# vco__amp_twg.net
KiCad netlist of a schematic drawn in EAGLE
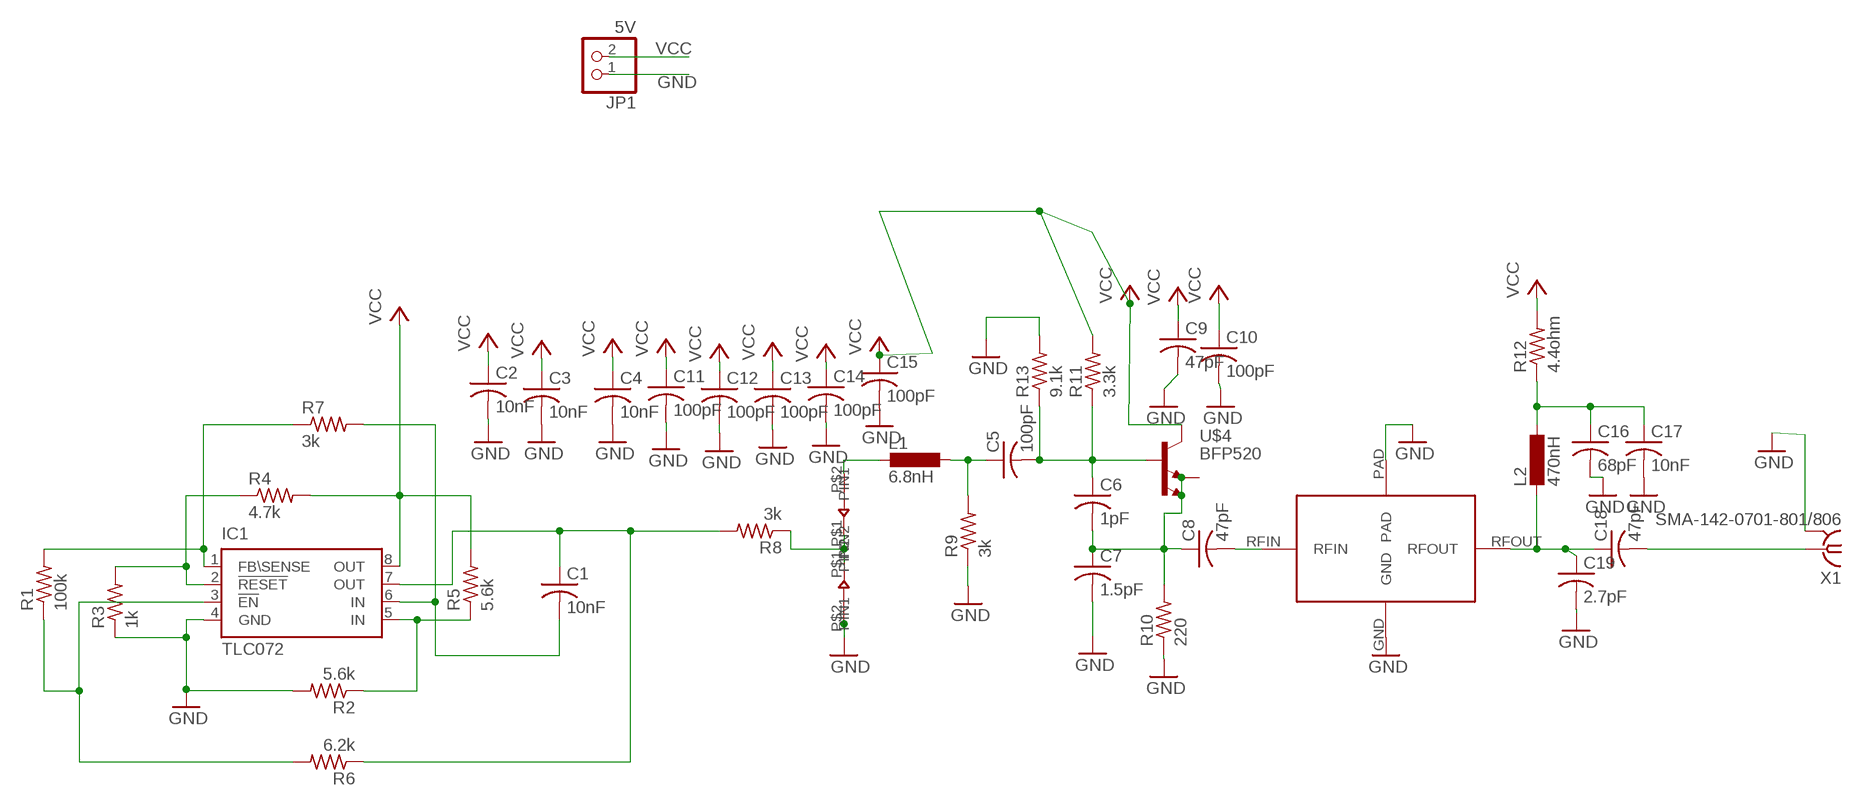
[diagram p0: schematic, sheet 1]

(export (version "E")
  (design (tool "Eeschema 10.0.6"))
  (components
    (comp (ref "C1")
      (value "10nF")
      (footprint "eagle-import:C0603")
      (libsource (lib "eagle-import") (part "resistor_C-USC0603"))
    )
    (comp (ref "C2")
      (value "10nF")
      (footprint "eagle-import:C0603")
      (libsource (lib "eagle-import") (part "resistor_C-USC0603"))
    )
    (comp (ref "C3")
      (value "10nF")
      (footprint "eagle-import:C0603")
      (libsource (lib "eagle-import") (part "resistor_C-USC0603"))
    )
    (comp (ref "C4")
      (value "10nF")
      (footprint "eagle-import:C0603")
      (libsource (lib "eagle-import") (part "resistor_C-USC0603"))
    )
    (comp (ref "C5")
      (value "100pF")
      (footprint "eagle-import:C0603")
      (libsource (lib "eagle-import") (part "resistor_C-USC0603"))
    )
    (comp (ref "C6")
      (value "1pF")
      (footprint "eagle-import:C0603")
      (libsource (lib "eagle-import") (part "resistor_C-USC0603"))
    )
    (comp (ref "C7")
      (value "1.5pF")
      (footprint "eagle-import:C0603")
      (libsource (lib "eagle-import") (part "resistor_C-USC0603"))
    )
    (comp (ref "C8")
      (value "47pF")
      (footprint "eagle-import:C0603")
      (libsource (lib "eagle-import") (part "resistor_C-USC0603"))
    )
    (comp (ref "C9")
      (value "47pF")
      (footprint "eagle-import:C0603")
      (libsource (lib "eagle-import") (part "resistor_C-USC0603"))
    )
    (comp (ref "C10")
      (value "100pF")
      (footprint "eagle-import:C0603")
      (libsource (lib "eagle-import") (part "resistor_C-USC0603"))
    )
    (comp (ref "C11")
      (value "100pF")
      (footprint "eagle-import:C0603")
      (libsource (lib "eagle-import") (part "resistor_C-USC0603"))
    )
    (comp (ref "C12")
      (value "100pF")
      (footprint "eagle-import:C0603")
      (libsource (lib "eagle-import") (part "resistor_C-USC0603"))
    )
    (comp (ref "C13")
      (value "100pF")
      (footprint "eagle-import:C0603")
      (libsource (lib "eagle-import") (part "resistor_C-USC0603"))
    )
    (comp (ref "C14")
      (value "100pF")
      (footprint "eagle-import:C0603")
      (libsource (lib "eagle-import") (part "resistor_C-USC0603"))
    )
    (comp (ref "C15")
      (value "100pF")
      (footprint "eagle-import:C0603")
      (libsource (lib "eagle-import") (part "resistor_C-USC0603"))
    )
    (comp (ref "C16")
      (value "68pF")
      (footprint "eagle-import:C0603")
      (libsource (lib "eagle-import") (part "resistor_C-USC0603"))
    )
    (comp (ref "C17")
      (value "10nF")
      (footprint "eagle-import:C0603")
      (libsource (lib "eagle-import") (part "resistor_C-USC0603"))
    )
    (comp (ref "C18")
      (value "47pF")
      (footprint "eagle-import:C0603")
      (libsource (lib "eagle-import") (part "resistor_C-USC0603"))
    )
    (comp (ref "C19")
      (value "2.7pF")
      (footprint "eagle-import:C0603")
      (libsource (lib "eagle-import") (part "C-USC0603"))
    )
    (comp (ref "IC1")
      (value "TLC072")
      (footprint "eagle-import:SOP-08")
      (fields (field (name "MF") "TEXAS INSTRUMENT CONNECTORS") (field (name "MPN") "TPS77301DGK"))
      (libsource (lib "eagle-import") (part "TPS77301"))
    )
    (comp (ref "JP1")
      (value "5V")
      (footprint "eagle-import:1X02")
      (libsource (lib "eagle-import") (part "PINHD-1X2"))
    )
    (comp (ref "L1")
      (value "6.8nH")
      (footprint "eagle-import:L0603")
      (libsource (lib "eagle-import") (part "L-EUL0603"))
    )
    (comp (ref "L2")
      (value "470nH")
      (footprint "eagle-import:L0603")
      (libsource (lib "eagle-import") (part "L-EUL0603"))
    )
    (comp (ref "R1")
      (value "100k")
      (footprint "eagle-import:R0603")
      (libsource (lib "eagle-import") (part "R-US_R0603"))
    )
    (comp (ref "R2")
      (value "5.6k")
      (footprint "eagle-import:R0603")
      (libsource (lib "eagle-import") (part "R-US_R0603"))
    )
    (comp (ref "R3")
      (value "1k")
      (footprint "eagle-import:R0603")
      (libsource (lib "eagle-import") (part "R-US_R0603"))
    )
    (comp (ref "R4")
      (value "4.7k")
      (footprint "eagle-import:R0603")
      (libsource (lib "eagle-import") (part "R-US_R0603"))
    )
    (comp (ref "R5")
      (value "5.6k")
      (footprint "eagle-import:R0603")
      (libsource (lib "eagle-import") (part "R-US_R0603"))
    )
    (comp (ref "R6")
      (value "6.2k")
      (footprint "eagle-import:R0603")
      (libsource (lib "eagle-import") (part "R-US_R0603"))
    )
    (comp (ref "R7")
      (value "3k")
      (footprint "eagle-import:R0603")
      (libsource (lib "eagle-import") (part "R-US_R0603"))
    )
    (comp (ref "R8")
      (value "3k")
      (footprint "eagle-import:R0603")
      (libsource (lib "eagle-import") (part "R-US_R0603"))
    )
    (comp (ref "R9")
      (value "3k")
      (footprint "eagle-import:R0603")
      (libsource (lib "eagle-import") (part "R-US_R0603"))
    )
    (comp (ref "R10")
      (value "220")
      (footprint "eagle-import:R0603")
      (libsource (lib "eagle-import") (part "R-US_R0603"))
    )
    (comp (ref "R11")
      (value "3.3k")
      (footprint "eagle-import:R0603")
      (libsource (lib "eagle-import") (part "R-US_R0603"))
    )
    (comp (ref "R12")
      (value "4.4ohm")
      (footprint "eagle-import:R0603")
      (libsource (lib "eagle-import") (part "R-US_R0603"))
    )
    (comp (ref "R13")
      (value "9.1k")
      (footprint "eagle-import:R0603")
      (libsource (lib "eagle-import") (part "R-US_R0603"))
    )
    (comp (ref "U$1")
      (value "BBY5702")
      (footprint "eagle-import:BBY5702")
      (libsource (lib "eagle-import") (part "BBY5702"))
    )
    (comp (ref "U$2")
      (value "MMG3001")
      (footprint "eagle-import:SOT-89")
      (libsource (lib "eagle-import") (part "MMG3001"))
    )
    (comp (ref "U$4")
      (value "BFP520")
      (footprint "eagle-import:SOT343")
      (libsource (lib "eagle-import") (part "BFP520"))
    )
    (comp (ref "U$5")
      (value "BBY5702")
      (footprint "eagle-import:BBY5702")
      (libsource (lib "eagle-import") (part "BBY5702"))
    )
    (comp (ref "X1")
      (value "SMA-142-0701-801/806")
      (footprint "eagle-import:J502-ND-142-0701-801_806")
      (fields (field (name "MF") "JOHNSON COMPONENTS") (field (name "MPN") "142-0701-801"))
      (libsource (lib "eagle-import") (part "SMA-142-0701-801/806"))
    )
  )
  (nets
    (net (code "1") (name "GND") (class "Default")
      (node (ref "C10") (pin "2") (pinfunction "2_2") (pintype "passive"))
      (node (ref "C11") (pin "2") (pinfunction "2_2") (pintype "passive"))
      (node (ref "C12") (pin "2") (pinfunction "2_2") (pintype "passive"))
      (node (ref "C13") (pin "2") (pinfunction "2_2") (pintype "passive"))
      (node (ref "C14") (pin "2") (pinfunction "2_2") (pintype "passive"))
      (node (ref "C15") (pin "2") (pinfunction "2_2") (pintype "passive"))
      (node (ref "C16") (pin "2") (pinfunction "2_2") (pintype "passive"))
      (node (ref "C17") (pin "2") (pinfunction "2_2") (pintype "passive"))
      (node (ref "C19") (pin "2") (pinfunction "2_2") (pintype "passive"))
      (node (ref "C2") (pin "2") (pinfunction "2_2") (pintype "passive"))
      (node (ref "C3") (pin "2") (pinfunction "2_2") (pintype "passive"))
      (node (ref "C4") (pin "2") (pinfunction "2_2") (pintype "passive"))
      (node (ref "C7") (pin "2") (pinfunction "2_2") (pintype "passive"))
      (node (ref "C9") (pin "2") (pinfunction "2_2") (pintype "passive"))
      (node (ref "IC1") (pin "4") (pinfunction "GND_4") (pintype "power_in"))
      (node (ref "JP1") (pin "1") (pinfunction "1_1") (pintype "passive"))
      (node (ref "R10") (pin "1") (pinfunction "1_1") (pintype "passive"))
      (node (ref "R13") (pin "2") (pinfunction "2_2") (pintype "passive"))
      (node (ref "R2") (pin "2") (pinfunction "2_2") (pintype "passive"))
      (node (ref "R3") (pin "1") (pinfunction "1_1") (pintype "passive"))
      (node (ref "R9") (pin "1") (pinfunction "1_1") (pintype "passive"))
      (node (ref "U$2") (pin "GND") (pinfunction "GND_GND") (pintype "bidirectional"))
      (node (ref "U$2") (pin "PAD") (pinfunction "PAD_PAD") (pintype "bidirectional"))
      (node (ref "U$5") (pin "P$2") (pinfunction "PIN2_P$2") (pintype "bidirectional"))
      (node (ref "X1") (pin "G@1") (pinfunction "2_G@1") (pintype "passive"))
      (node (ref "X1") (pin "G@2") (pinfunction "2_G@2") (pintype "passive"))
      (node (ref "X1") (pin "G@3") (pinfunction "2_G@3") (pintype "passive"))
      (node (ref "X1") (pin "G@4") (pinfunction "2_G@4") (pintype "passive"))
    )
    (net (code "2") (name "Net-(C1-Pad1)") (class "Default")
      (node (ref "C1") (pin "1") (pinfunction "1_1") (pintype "passive"))
      (node (ref "IC1") (pin "7") (pinfunction "OUT_7") (pintype "output"))
      (node (ref "R6") (pin "1") (pinfunction "1_1") (pintype "passive"))
      (node (ref "R8") (pin "2") (pinfunction "2_2") (pintype "passive"))
    )
    (net (code "3") (name "Net-(C1-Pad2)") (class "Default")
      (node (ref "C1") (pin "2") (pinfunction "2_2") (pintype "passive"))
      (node (ref "IC1") (pin "6") (pinfunction "IN_6") (pintype "input"))
      (node (ref "R7") (pin "2") (pinfunction "2_2") (pintype "passive"))
    )
    (net (code "4") (name "Net-(C5-Pad1)") (class "Default")
      (node (ref "C5") (pin "1") (pinfunction "1_1") (pintype "passive"))
      (node (ref "L1") (pin "1") (pinfunction "1_1") (pintype "passive"))
      (node (ref "R9") (pin "2") (pinfunction "2_2") (pintype "passive"))
    )
    (net (code "5") (name "Net-(C8-Pad2)") (class "Default")
      (node (ref "C8") (pin "2") (pinfunction "2_2") (pintype "passive"))
      (node (ref "U$2") (pin "RFIN") (pinfunction "RFIN_RFIN") (pintype "bidirectional"))
    )
    (net (code "6") (name "Net-(C16-Pad1)") (class "Default")
      (node (ref "C16") (pin "1") (pinfunction "1_1") (pintype "passive"))
      (node (ref "C17") (pin "1") (pinfunction "1_1") (pintype "passive"))
      (node (ref "L2") (pin "1") (pinfunction "1_1") (pintype "passive"))
      (node (ref "R12") (pin "1") (pinfunction "1_1") (pintype "passive"))
    )
    (net (code "7") (name "Net-(C18-Pad1)") (class "Default")
      (node (ref "C18") (pin "1") (pinfunction "1_1") (pintype "passive"))
      (node (ref "C19") (pin "1") (pinfunction "1_1") (pintype "passive"))
      (node (ref "L2") (pin "2") (pinfunction "2_2") (pintype "passive"))
      (node (ref "U$2") (pin "RFOUT") (pinfunction "RFOUT_RFOUT") (pintype "bidirectional"))
    )
    (net (code "8") (name "Net-(C18-Pad2)") (class "Default")
      (node (ref "C18") (pin "2") (pinfunction "2_2") (pintype "passive"))
      (node (ref "X1") (pin "1") (pinfunction "1_1") (pintype "passive"))
    )
    (net (code "9") (name "Net-(IC1-FB\\SENSE)") (class "Default")
      (node (ref "IC1") (pin "1") (pinfunction "FB\\SENSE_1") (pintype "input"))
      (node (ref "R1") (pin "2") (pinfunction "2_2") (pintype "passive"))
      (node (ref "R7") (pin "1") (pinfunction "1_1") (pintype "passive"))
    )
    (net (code "10") (name "Net-(IC1-IN-Pad5)") (class "Default")
      (node (ref "IC1") (pin "5") (pinfunction "IN_5") (pintype "input"))
      (node (ref "R2") (pin "1") (pinfunction "1_1") (pintype "passive"))
      (node (ref "R5") (pin "1") (pinfunction "1_1") (pintype "passive"))
    )
    (net (code "11") (name "Net-(IC1-~{EN})") (class "Default")
      (node (ref "IC1") (pin "3") (pinfunction "~{EN}_3") (pintype "input"))
      (node (ref "R1") (pin "1") (pinfunction "1_1") (pintype "passive"))
      (node (ref "R6") (pin "2") (pinfunction "2_2") (pintype "passive"))
    )
    (net (code "12") (name "Net-(IC1-~{RESET})") (class "Default")
      (node (ref "IC1") (pin "2") (pinfunction "~{RESET}_2") (pintype "input"))
      (node (ref "R3") (pin "2") (pinfunction "2_2") (pintype "passive"))
      (node (ref "R4") (pin "1") (pinfunction "1_1") (pintype "passive"))
    )
    (net (code "13") (name "Net-(U$1-PIN1)") (class "Default")
      (node (ref "R8") (pin "1") (pinfunction "1_1") (pintype "passive"))
      (node (ref "U$1") (pin "P$1") (pinfunction "PIN1_P$1") (pintype "bidirectional"))
      (node (ref "U$5") (pin "P$1") (pinfunction "PIN1_P$1") (pintype "bidirectional"))
    )
    (net (code "14") (name "Net-(U$1-PIN2)") (class "Default")
      (node (ref "L1") (pin "2") (pinfunction "2_2") (pintype "passive"))
      (node (ref "U$1") (pin "P$2") (pinfunction "PIN2_P$2") (pintype "bidirectional"))
    )
    (net (code "15") (name "Net-(U$4-B)") (class "Default")
      (node (ref "C5") (pin "2") (pinfunction "2_2") (pintype "passive"))
      (node (ref "C6") (pin "1") (pinfunction "1_1") (pintype "passive"))
      (node (ref "R11") (pin "1") (pinfunction "1_1") (pintype "passive"))
      (node (ref "R13") (pin "1") (pinfunction "1_1") (pintype "passive"))
      (node (ref "U$4") (pin "1") (pinfunction "B_1") (pintype "passive"))
    )
    (net (code "16") (name "Net-(U$4-E1)") (class "Default")
      (node (ref "C6") (pin "2") (pinfunction "2_2") (pintype "passive"))
      (node (ref "C7") (pin "1") (pinfunction "1_1") (pintype "passive"))
      (node (ref "C8") (pin "1") (pinfunction "1_1") (pintype "passive"))
      (node (ref "R10") (pin "2") (pinfunction "2_2") (pintype "passive"))
      (node (ref "U$4") (pin "2") (pinfunction "E1_2") (pintype "passive"))
      (node (ref "U$4") (pin "4") (pinfunction "E2_4") (pintype "passive"))
    )
    (net (code "17") (name "VCC") (class "Default")
      (node (ref "C10") (pin "1") (pinfunction "1_1") (pintype "passive"))
      (node (ref "C11") (pin "1") (pinfunction "1_1") (pintype "passive"))
      (node (ref "C12") (pin "1") (pinfunction "1_1") (pintype "passive"))
      (node (ref "C13") (pin "1") (pinfunction "1_1") (pintype "passive"))
      (node (ref "C14") (pin "1") (pinfunction "1_1") (pintype "passive"))
      (node (ref "C15") (pin "1") (pinfunction "1_1") (pintype "passive"))
      (node (ref "C2") (pin "1") (pinfunction "1_1") (pintype "passive"))
      (node (ref "C3") (pin "1") (pinfunction "1_1") (pintype "passive"))
      (node (ref "C4") (pin "1") (pinfunction "1_1") (pintype "passive"))
      (node (ref "C9") (pin "1") (pinfunction "1_1") (pintype "passive"))
      (node (ref "IC1") (pin "8") (pinfunction "OUT_8") (pintype "passive"))
      (node (ref "JP1") (pin "2") (pinfunction "2_2") (pintype "passive"))
      (node (ref "R11") (pin "2") (pinfunction "2_2") (pintype "passive"))
      (node (ref "R12") (pin "2") (pinfunction "2_2") (pintype "passive"))
      (node (ref "R4") (pin "2") (pinfunction "2_2") (pintype "passive"))
      (node (ref "R5") (pin "2") (pinfunction "2_2") (pintype "passive"))
      (node (ref "U$4") (pin "3") (pinfunction "C_3") (pintype "passive"))
    )
  )
)
